# Pyr0-Piezo-FFC-Direct-Creality-X-Board_2.net
KiCad netlist of a schematic drawn in EAGLE
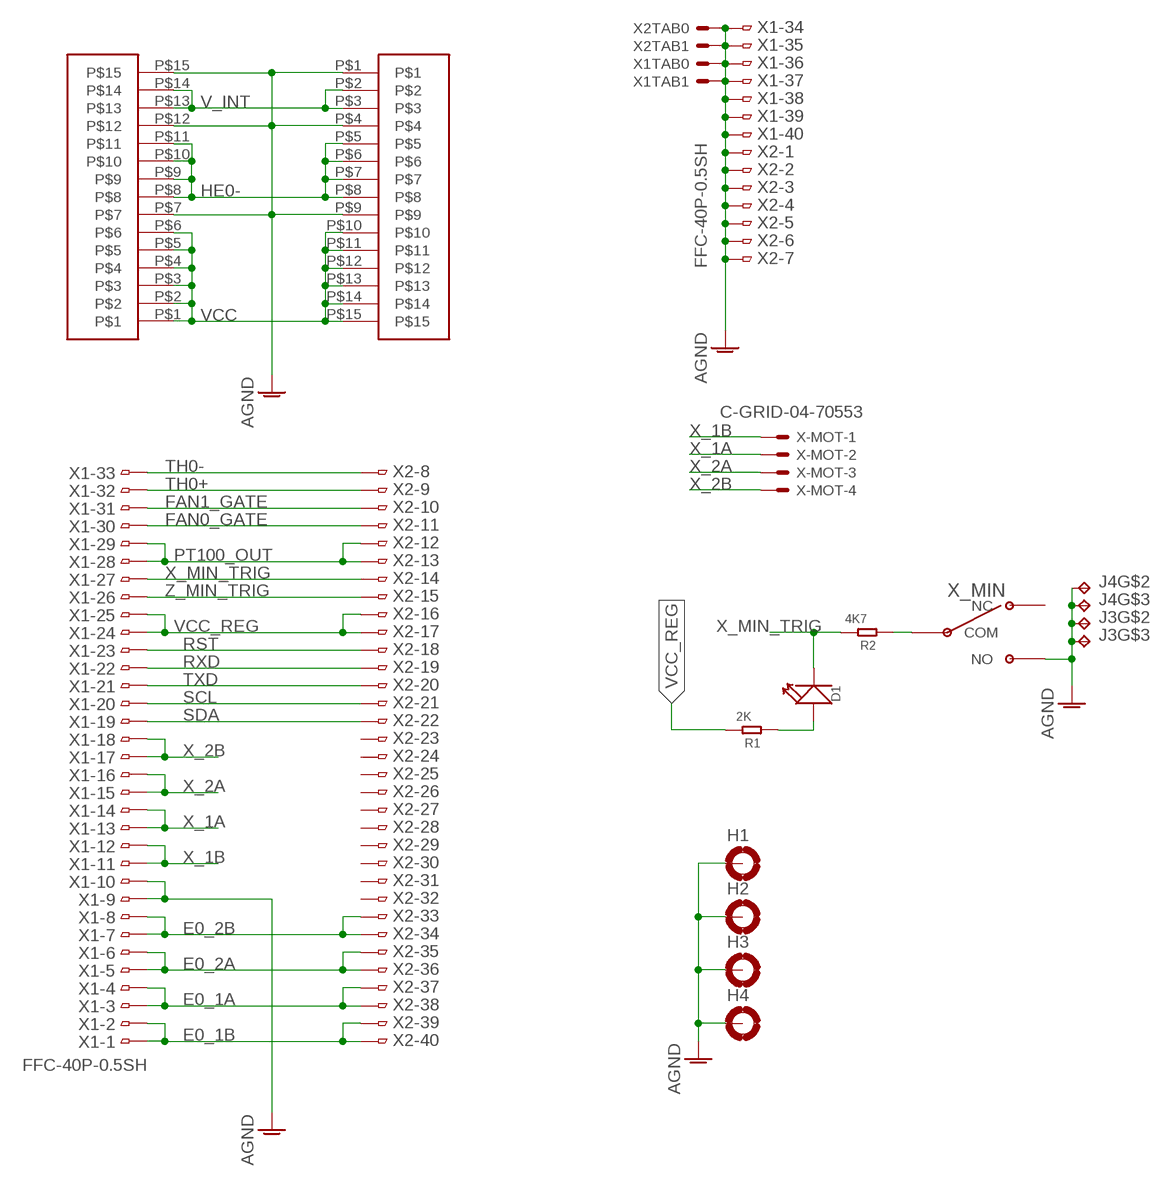
[diagram p0: schematic, sheet 1]

(export (version "E")
  (design (tool "Eeschema 10.0.6"))
  (components
    (comp (ref "D1")
      (value "SEEED-LED_SMD-LED-CLEAR-BLUE(0603)LED_0603")
      (footprint "eagle-import:SEEED-LED_LED-0603")
      (libsource (lib "eagle-import") (part "SEEED-LED_SMD-LED-CLEAR-BLUE(0603)LED_0603"))
    )
    (comp (ref "H1")
      (value "HOLES_MOUNT-PAD-ROUND3.2")
      (footprint "eagle-import:HOLES_3,2-PAD")
      (libsource (lib "eagle-import") (part "HOLES_MOUNT-PAD-ROUND3.2"))
    )
    (comp (ref "H2")
      (value "HOLES_MOUNT-PAD-ROUND3.2")
      (footprint "eagle-import:HOLES_3,2-PAD")
      (libsource (lib "eagle-import") (part "HOLES_MOUNT-PAD-ROUND3.2"))
    )
    (comp (ref "H3")
      (value "HOLES_MOUNT-PAD-ROUND3.2")
      (footprint "eagle-import:HOLES_3,2-PAD")
      (libsource (lib "eagle-import") (part "HOLES_MOUNT-PAD-ROUND3.2"))
    )
    (comp (ref "H4")
      (value "HOLES_MOUNT-PAD-ROUND3.2")
      (footprint "eagle-import:HOLES_3,2-PAD")
      (libsource (lib "eagle-import") (part "HOLES_MOUNT-PAD-ROUND3.2"))
    )
    (comp (ref "J3")
      (value "FFC-15P-1MM")
      (footprint "eagle-import:FFC-15P-1MM")
      (libsource (lib "eagle-import") (part "FFC-15P-1MM"))
    )
    (comp (ref "J4")
      (value "FFC-15P-1MM")
      (footprint "eagle-import:FFC-15P-1MM")
      (libsource (lib "eagle-import") (part "FFC-15P-1MM"))
    )
    (comp (ref "R1")
      (value "2K")
      (footprint "eagle-import:R0805")
      (fields (field (name "MPN") "RC0805JR-072KL"))
      (libsource (lib "eagle-import") (part "SMD-RES-2K-5%-1/8W(0805)"))
    )
    (comp (ref "R2")
      (value "4K7")
      (footprint "eagle-import:R0805")
      (fields (field (name "MPN") "RC0805JR-072KL"))
      (libsource (lib "eagle-import") (part "SMD-RES-2K-5%-1/8W(0805)"))
    )
    (comp (ref "X-MOT")
      (value "C-GRID-04-70553")
      (footprint "eagle-import:70553-04")
      (fields (field (name "MF") "MOLEX"))
      (libsource (lib "eagle-import") (part "C-GRID-04-70553"))
    )
    (comp (ref "X1")
      (value "FFC-40P-0.5SH")
      (footprint "eagle-import:FH12-40S-0.5SH")
      (fields (field (name "MPN") "FH12-40S-0.5SH(55)"))
      (libsource (lib "eagle-import") (part "FFC-40P-0.5SH"))
    )
    (comp (ref "X2")
      (value "FFC-40P-0.5SH")
      (footprint "eagle-import:FH12-40S-0.5SH")
      (fields (field (name "MPN") "FH12-40S-0.5SH(55)"))
      (libsource (lib "eagle-import") (part "FFC-40P-0.5SH"))
    )
    (comp (ref "X_MIN")
      (value "LIMIT_SWITCH")
      (footprint "eagle-import:LIMIT_SWITCH_BRIDGE")
      (libsource (lib "eagle-import") (part "LIMIT_SWITCH"))
    )
  )
  (nets
    (net (code "1") (name "/E0_1A") (class "Default")
      (node (ref "X1") (pin "3") (pinfunction "1_3") (pintype "passive"))
      (node (ref "X1") (pin "4") (pinfunction "1_4") (pintype "passive"))
      (node (ref "X2") (pin "37") (pinfunction "1_37") (pintype "passive"))
      (node (ref "X2") (pin "38") (pinfunction "1_38") (pintype "passive"))
    )
    (net (code "2") (name "/E0_1B") (class "Default")
      (node (ref "X1") (pin "1") (pinfunction "1_1") (pintype "passive"))
      (node (ref "X1") (pin "2") (pinfunction "1_2") (pintype "passive"))
      (node (ref "X2") (pin "39") (pinfunction "1_39") (pintype "passive"))
      (node (ref "X2") (pin "40") (pinfunction "1_40") (pintype "passive"))
    )
    (net (code "3") (name "/E0_2A") (class "Default")
      (node (ref "X1") (pin "5") (pinfunction "1_5") (pintype "passive"))
      (node (ref "X1") (pin "6") (pinfunction "1_6") (pintype "passive"))
      (node (ref "X2") (pin "35") (pinfunction "1_35") (pintype "passive"))
      (node (ref "X2") (pin "36") (pinfunction "1_36") (pintype "passive"))
    )
    (net (code "4") (name "/E0_2B") (class "Default")
      (node (ref "X1") (pin "7") (pinfunction "1_7") (pintype "passive"))
      (node (ref "X1") (pin "8") (pinfunction "1_8") (pintype "passive"))
      (node (ref "X2") (pin "33") (pinfunction "1_33") (pintype "passive"))
      (node (ref "X2") (pin "34") (pinfunction "1_34") (pintype "passive"))
    )
    (net (code "5") (name "/FAN0_GATE") (class "Default")
      (node (ref "X1") (pin "30") (pinfunction "1_30") (pintype "passive"))
      (node (ref "X2") (pin "11") (pinfunction "1_11") (pintype "passive"))
    )
    (net (code "6") (name "/FAN1_GATE") (class "Default")
      (node (ref "X1") (pin "31") (pinfunction "1_31") (pintype "passive"))
      (node (ref "X2") (pin "10") (pinfunction "1_10") (pintype "passive"))
    )
    (net (code "7") (name "/HE0-") (class "Default")
      (node (ref "J3") (pin "P$10") (pinfunction "P$10_P$10") (pintype "bidirectional"))
      (node (ref "J3") (pin "P$11") (pinfunction "P$11_P$11") (pintype "bidirectional"))
      (node (ref "J3") (pin "P$8") (pinfunction "P$8_P$8") (pintype "bidirectional"))
      (node (ref "J3") (pin "P$9") (pinfunction "P$9_P$9") (pintype "bidirectional"))
      (node (ref "J4") (pin "P$5") (pinfunction "P$5_P$5") (pintype "bidirectional"))
      (node (ref "J4") (pin "P$6") (pinfunction "P$6_P$6") (pintype "bidirectional"))
      (node (ref "J4") (pin "P$7") (pinfunction "P$7_P$7") (pintype "bidirectional"))
      (node (ref "J4") (pin "P$8") (pinfunction "P$8_P$8") (pintype "bidirectional"))
    )
    (net (code "8") (name "/PT100_OUT") (class "Default")
      (node (ref "X1") (pin "28") (pinfunction "1_28") (pintype "passive"))
      (node (ref "X1") (pin "29") (pinfunction "1_29") (pintype "passive"))
      (node (ref "X2") (pin "12") (pinfunction "1_12") (pintype "passive"))
      (node (ref "X2") (pin "13") (pinfunction "1_13") (pintype "passive"))
    )
    (net (code "9") (name "/RST") (class "Default")
      (node (ref "X1") (pin "23") (pinfunction "1_23") (pintype "passive"))
      (node (ref "X2") (pin "18") (pinfunction "1_18") (pintype "passive"))
    )
    (net (code "10") (name "/RXD") (class "Default")
      (node (ref "X1") (pin "22") (pinfunction "1_22") (pintype "passive"))
      (node (ref "X2") (pin "19") (pinfunction "1_19") (pintype "passive"))
    )
    (net (code "11") (name "/SCL") (class "Default")
      (node (ref "X1") (pin "20") (pinfunction "1_20") (pintype "passive"))
      (node (ref "X2") (pin "21") (pinfunction "1_21") (pintype "passive"))
    )
    (net (code "12") (name "/SDA") (class "Default")
      (node (ref "X1") (pin "19") (pinfunction "1_19") (pintype "passive"))
      (node (ref "X2") (pin "22") (pinfunction "1_22") (pintype "passive"))
    )
    (net (code "13") (name "/TH0+") (class "Default")
      (node (ref "X1") (pin "32") (pinfunction "1_32") (pintype "passive"))
      (node (ref "X2") (pin "9") (pinfunction "1_9") (pintype "passive"))
    )
    (net (code "14") (name "/TH0-") (class "Default")
      (node (ref "X1") (pin "33") (pinfunction "1_33") (pintype "passive"))
      (node (ref "X2") (pin "8") (pinfunction "1_8") (pintype "passive"))
    )
    (net (code "15") (name "/TXD") (class "Default")
      (node (ref "X1") (pin "21") (pinfunction "1_21") (pintype "passive"))
      (node (ref "X2") (pin "20") (pinfunction "1_20") (pintype "passive"))
    )
    (net (code "16") (name "/VCC") (class "Default")
      (node (ref "J3") (pin "P$1") (pinfunction "P$1_P$1") (pintype "bidirectional"))
      (node (ref "J3") (pin "P$2") (pinfunction "P$2_P$2") (pintype "bidirectional"))
      (node (ref "J3") (pin "P$3") (pinfunction "P$3_P$3") (pintype "bidirectional"))
      (node (ref "J3") (pin "P$4") (pinfunction "P$4_P$4") (pintype "bidirectional"))
      (node (ref "J3") (pin "P$5") (pinfunction "P$5_P$5") (pintype "bidirectional"))
      (node (ref "J3") (pin "P$6") (pinfunction "P$6_P$6") (pintype "bidirectional"))
      (node (ref "J4") (pin "P$10") (pinfunction "P$10_P$10") (pintype "bidirectional"))
      (node (ref "J4") (pin "P$11") (pinfunction "P$11_P$11") (pintype "bidirectional"))
      (node (ref "J4") (pin "P$12") (pinfunction "P$12_P$12") (pintype "bidirectional"))
      (node (ref "J4") (pin "P$13") (pinfunction "P$13_P$13") (pintype "bidirectional"))
      (node (ref "J4") (pin "P$14") (pinfunction "P$14_P$14") (pintype "bidirectional"))
      (node (ref "J4") (pin "P$15") (pinfunction "P$15_P$15") (pintype "bidirectional"))
    )
    (net (code "17") (name "/V_INT") (class "Default")
      (node (ref "J3") (pin "P$13") (pinfunction "P$13_P$13") (pintype "bidirectional"))
      (node (ref "J3") (pin "P$14") (pinfunction "P$14_P$14") (pintype "bidirectional"))
      (node (ref "J4") (pin "P$2") (pinfunction "P$2_P$2") (pintype "bidirectional"))
      (node (ref "J4") (pin "P$3") (pinfunction "P$3_P$3") (pintype "bidirectional"))
    )
    (net (code "18") (name "/X_1A") (class "Default")
      (node (ref "X-MOT") (pin "2") (pinfunction "S_2") (pintype "passive"))
      (node (ref "X1") (pin "13") (pinfunction "1_13") (pintype "passive"))
      (node (ref "X1") (pin "14") (pinfunction "1_14") (pintype "passive"))
    )
    (net (code "19") (name "/X_1B") (class "Default")
      (node (ref "X-MOT") (pin "1") (pinfunction "S_1") (pintype "passive"))
      (node (ref "X1") (pin "11") (pinfunction "1_11") (pintype "passive"))
      (node (ref "X1") (pin "12") (pinfunction "1_12") (pintype "passive"))
    )
    (net (code "20") (name "/X_2A") (class "Default")
      (node (ref "X-MOT") (pin "3") (pinfunction "S_3") (pintype "passive"))
      (node (ref "X1") (pin "15") (pinfunction "1_15") (pintype "passive"))
      (node (ref "X1") (pin "16") (pinfunction "1_16") (pintype "passive"))
    )
    (net (code "21") (name "/X_2B") (class "Default")
      (node (ref "X-MOT") (pin "4") (pinfunction "S_4") (pintype "passive"))
      (node (ref "X1") (pin "17") (pinfunction "1_17") (pintype "passive"))
      (node (ref "X1") (pin "18") (pinfunction "1_18") (pintype "passive"))
    )
    (net (code "22") (name "/X_MIN_TRIG") (class "Default")
      (node (ref "D1") (pin "-") (pinfunction "-_-") (pintype "passive"))
      (node (ref "R2") (pin "2") (pinfunction "2_2") (pintype "passive"))
      (node (ref "X1") (pin "27") (pinfunction "1_27") (pintype "passive"))
      (node (ref "X2") (pin "14") (pinfunction "1_14") (pintype "passive"))
    )
    (net (code "23") (name "/Z_MIN_TRIG") (class "Default")
      (node (ref "X1") (pin "26") (pinfunction "1_26") (pintype "passive"))
      (node (ref "X2") (pin "15") (pinfunction "1_15") (pintype "passive"))
    )
    (net (code "24") (name "AGND") (class "Default")
      (node (ref "H1") (pin "B3,2") (pinfunction "MOUNT_B3,2") (pintype "passive"))
      (node (ref "H2") (pin "B3,2") (pinfunction "MOUNT_B3,2") (pintype "passive"))
      (node (ref "H3") (pin "B3,2") (pinfunction "MOUNT_B3,2") (pintype "passive"))
      (node (ref "H4") (pin "B3,2") (pinfunction "MOUNT_B3,2") (pintype "passive"))
      (node (ref "J3") (pin "P$12") (pinfunction "P$12_P$12") (pintype "bidirectional"))
      (node (ref "J3") (pin "P$15") (pinfunction "P$15_P$15") (pintype "bidirectional"))
      (node (ref "J3") (pin "P$16") (pinfunction "TP_P$16") (pintype "input"))
      (node (ref "J3") (pin "P$17") (pinfunction "TP_P$17") (pintype "input"))
      (node (ref "J3") (pin "P$7") (pinfunction "P$7_P$7") (pintype "bidirectional"))
      (node (ref "J4") (pin "P$1") (pinfunction "P$1_P$1") (pintype "bidirectional"))
      (node (ref "J4") (pin "P$16") (pinfunction "TP_P$16") (pintype "input"))
      (node (ref "J4") (pin "P$17") (pinfunction "TP_P$17") (pintype "input"))
      (node (ref "J4") (pin "P$4") (pinfunction "P$4_P$4") (pintype "bidirectional"))
      (node (ref "J4") (pin "P$9") (pinfunction "P$9_P$9") (pintype "bidirectional"))
      (node (ref "X1") (pin "10") (pinfunction "1_10") (pintype "passive"))
      (node (ref "X1") (pin "34") (pinfunction "1_34") (pintype "passive"))
      (node (ref "X1") (pin "35") (pinfunction "1_35") (pintype "passive"))
      (node (ref "X1") (pin "36") (pinfunction "1_36") (pintype "passive"))
      (node (ref "X1") (pin "37") (pinfunction "1_37") (pintype "passive"))
      (node (ref "X1") (pin "38") (pinfunction "1_38") (pintype "passive"))
      (node (ref "X1") (pin "39") (pinfunction "1_39") (pintype "passive"))
      (node (ref "X1") (pin "40") (pinfunction "1_40") (pintype "passive"))
      (node (ref "X1") (pin "9") (pinfunction "1_9") (pintype "passive"))
      (node (ref "X1") (pin "TAB0") (pinfunction "S_TAB0") (pintype "passive"))
      (node (ref "X1") (pin "TAB1") (pinfunction "S_TAB1") (pintype "passive"))
      (node (ref "X2") (pin "1") (pinfunction "1_1") (pintype "passive"))
      (node (ref "X2") (pin "2") (pinfunction "1_2") (pintype "passive"))
      (node (ref "X2") (pin "3") (pinfunction "1_3") (pintype "passive"))
      (node (ref "X2") (pin "4") (pinfunction "1_4") (pintype "passive"))
      (node (ref "X2") (pin "5") (pinfunction "1_5") (pintype "passive"))
      (node (ref "X2") (pin "6") (pinfunction "1_6") (pintype "passive"))
      (node (ref "X2") (pin "7") (pinfunction "1_7") (pintype "passive"))
      (node (ref "X2") (pin "TAB0") (pinfunction "S_TAB0") (pintype "passive"))
      (node (ref "X2") (pin "TAB1") (pinfunction "S_TAB1") (pintype "passive"))
      (node (ref "X_MIN") (pin "NO") (pinfunction "NO_NO") (pintype "bidirectional"))
    )
    (net (code "25") (name "Net-(D1-Pad+)") (class "Default")
      (node (ref "D1") (pin "+") (pinfunction "+_+") (pintype "passive"))
      (node (ref "R1") (pin "1") (pinfunction "1_1") (pintype "passive"))
    )
    (net (code "26") (name "Net-(R2-Pad1)") (class "Default")
      (node (ref "R2") (pin "1") (pinfunction "1_1") (pintype "passive"))
      (node (ref "X_MIN") (pin "COM") (pinfunction "COM_COM") (pintype "bidirectional"))
    )
    (net (code "27") (name "VCC_REG") (class "Default")
      (node (ref "R1") (pin "2") (pinfunction "2_2") (pintype "passive"))
      (node (ref "X1") (pin "24") (pinfunction "1_24") (pintype "passive"))
      (node (ref "X1") (pin "25") (pinfunction "1_25") (pintype "passive"))
      (node (ref "X2") (pin "16") (pinfunction "1_16") (pintype "passive"))
      (node (ref "X2") (pin "17") (pinfunction "1_17") (pintype "passive"))
    )
    (net (code "28") (name "unconnected-(X2P-1-Pad23)") (class "Default")
      (node (ref "X2") (pin "23") (pinfunction "1_23") (pintype "passive"))
    )
    (net (code "29") (name "unconnected-(X2Q-1-Pad24)") (class "Default")
      (node (ref "X2") (pin "24") (pinfunction "1_24") (pintype "passive"))
    )
    (net (code "30") (name "unconnected-(X2R-1-Pad25)") (class "Default")
      (node (ref "X2") (pin "25") (pinfunction "1_25") (pintype "passive"))
    )
    (net (code "31") (name "unconnected-(X2S-1-Pad26)") (class "Default")
      (node (ref "X2") (pin "26") (pinfunction "1_26") (pintype "passive"))
    )
    (net (code "32") (name "unconnected-(X2T-1-Pad27)") (class "Default")
      (node (ref "X2") (pin "27") (pinfunction "1_27") (pintype "passive"))
    )
    (net (code "33") (name "unconnected-(X2U-1-Pad28)") (class "Default")
      (node (ref "X2") (pin "28") (pinfunction "1_28") (pintype "passive"))
    )
    (net (code "34") (name "unconnected-(X2V-1-Pad29)") (class "Default")
      (node (ref "X2") (pin "29") (pinfunction "1_29") (pintype "passive"))
    )
    (net (code "35") (name "unconnected-(X2X-1-Pad30)") (class "Default")
      (node (ref "X2") (pin "30") (pinfunction "1_30") (pintype "passive"))
    )
    (net (code "36") (name "unconnected-(X2Y-1-Pad31)") (class "Default")
      (node (ref "X2") (pin "31") (pinfunction "1_31") (pintype "passive"))
    )
    (net (code "37") (name "unconnected-(X2Z-1-Pad32)") (class "Default")
      (node (ref "X2") (pin "32") (pinfunction "1_32") (pintype "passive"))
    )
    (net (code "38") (name "unconnected-(X_MIN-PadNC)") (class "Default")
      (node (ref "X_MIN") (pin "NC") (pinfunction "NC_NC") (pintype "bidirectional"))
    )
  )
)
